# v0_4.net
KiCad netlist of a schematic drawn in EAGLE
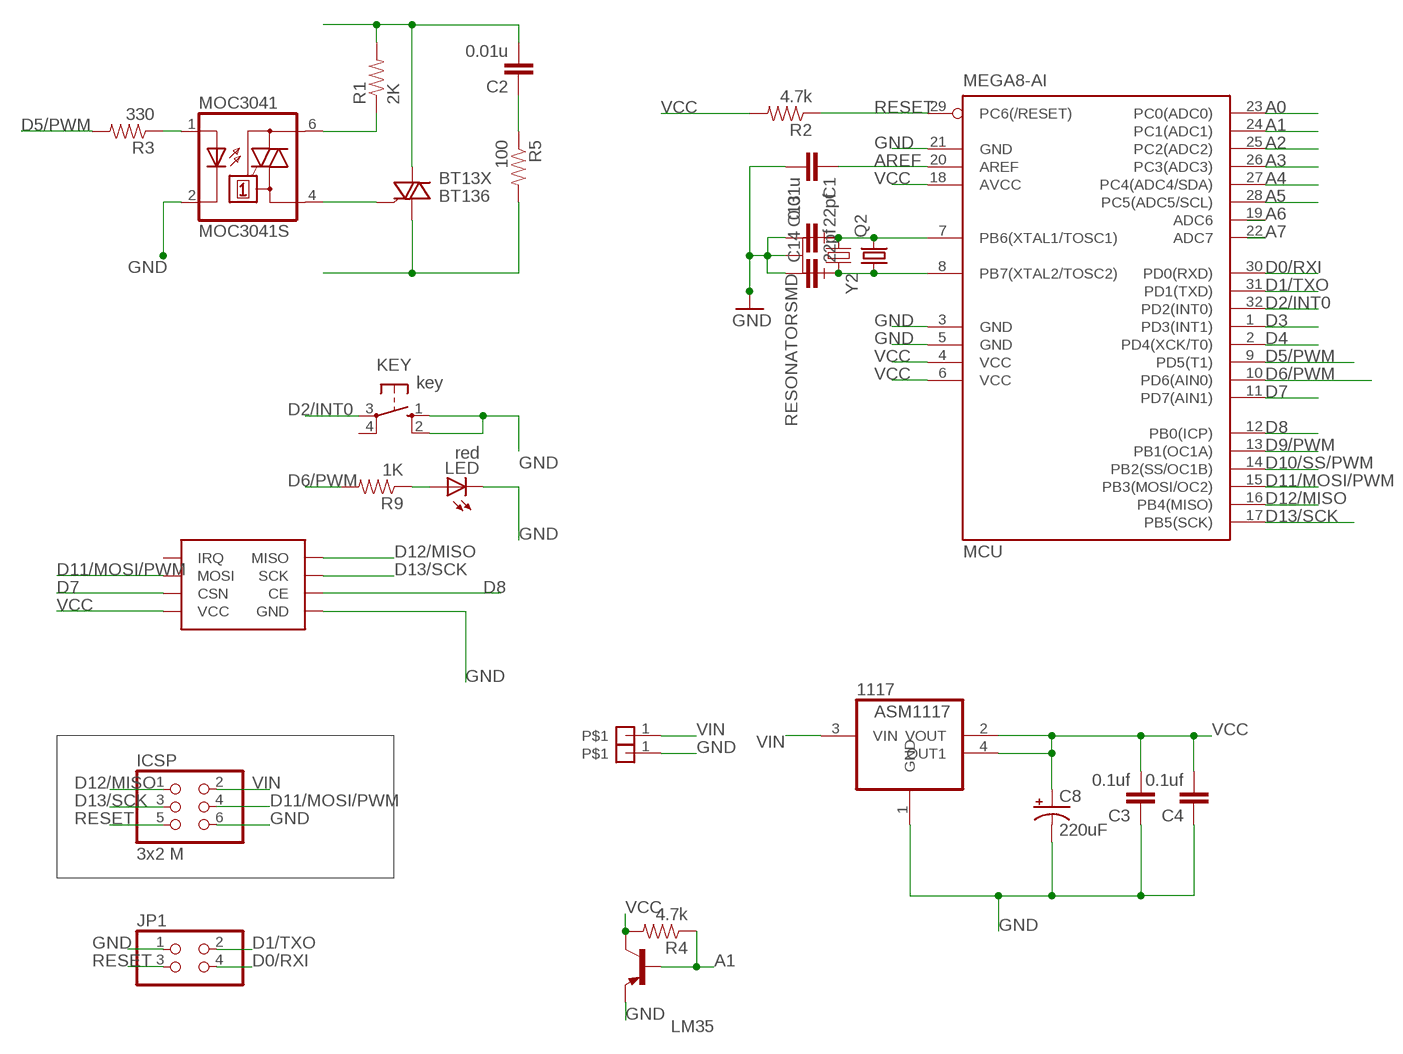
[diagram p0: schematic, sheet 1]

(export (version "E")
  (design (tool "Eeschema 10.0.6"))
  (components
    (comp (ref "1117")
      (value "ASM1117")
      (footprint "eagle-import:SOT223")
      (fields (field (name "MPN") "REG1117"))
      (libsource (lib "eagle-import") (part "ASM1117"))
    )
    (comp (ref "BT13X")
      (value "BT136")
      (footprint "eagle-import:TO252")
      (libsource (lib "eagle-import") (part "BT136"))
    )
    (comp (ref "C1")
      (value "0.01u")
      (footprint "eagle-import:0603-CAP")
      (libsource (lib "eagle-import") (part "MY2_CAP0603-CAP"))
    )
    (comp (ref "C2")
      (value "0.01u")
      (footprint "eagle-import:C050-024X044")
      (libsource (lib "eagle-import") (part "C-EU050-024X044"))
    )
    (comp (ref "C3")
      (value "0.1uf")
      (footprint "eagle-import:0603-CAP")
      (libsource (lib "eagle-import") (part "MY_CAP0603-CAP"))
    )
    (comp (ref "C4")
      (value "0.1uf")
      (footprint "eagle-import:0603-CAP")
      (libsource (lib "eagle-import") (part "MY_CAP0603-CAP"))
    )
    (comp (ref "C8")
      (value "220uF")
      (footprint "eagle-import:EIA3528")
      (libsource (lib "eagle-import") (part "CAP_POL3528"))
    )
    (comp (ref "C13")
      (value "22pf")
      (footprint "eagle-import:0603-CAP")
      (libsource (lib "eagle-import") (part "CAP0603-CAP"))
    )
    (comp (ref "C14")
      (value "22pf")
      (footprint "eagle-import:0603-CAP")
      (libsource (lib "eagle-import") (part "CAP0603-CAP"))
    )
    (comp (ref "ICSP")
      (value "3x2 M")
      (footprint "eagle-import:2X03")
      (libsource (lib "eagle-import") (part "PINHD-2X3"))
    )
    (comp (ref "JP1")
      (value "PINHD-2X2")
      (footprint "eagle-import:2X02")
      (libsource (lib "eagle-import") (part "PINHD-2X2"))
    )
    (comp (ref "KEY")
      (value "key")
      (footprint "eagle-import:B3F-10XX")
      (fields
        (field (name "MPN") "B3F-1000")
        (field (name "MPN_1") "B3F-1000")
        (field (name "OC_FARNELL") "176432")
        (field (name "OC_NEWARK") "36M3542")
      )
      (libsource (lib "eagle-import") (part "10-XX"))
    )
    (comp (ref "LED")
      (value "red")
      (footprint "eagle-import:LED3MM")
      (libsource (lib "eagle-import") (part "LED3MM"))
    )
    (comp (ref "LM35")
      (value "-PNP-TO92-E1")
      (footprint "eagle-import:TO92-E1")
      (libsource (lib "eagle-import") (part "-PNP-TO92-E1"))
    )
    (comp (ref "MCU")
      (value "MEGA8-AI")
      (footprint "eagle-import:TQFP32-08")
      (fields (field (name "MPN") "ATMEGA8-16AU"))
      (libsource (lib "eagle-import") (part "MEGA8-AI"))
    )
    (comp (ref "MOC3041")
      (value "MOC3041S")
      (footprint "eagle-import:DIL6-SMD")
      (fields
        (field (name "MF") "FAIRCHILD SEMICONDUCTOR")
        (field (name "MPN") "MOC3041S-M")
        (field (name "MF_1") "FAIRCHILD SEMICONDUCTOR")
        (field (name "MPN_1") "MOC3041S-M")
        (field (name "OC_NEWARK") "05C2885")
      )
      (libsource (lib "eagle-import") (part "MOC30S41"))
    )
    (comp (ref "Q2")
      (value "CRYSTALHC49S")
      (footprint "eagle-import:HC49_S")
      (libsource (lib "eagle-import") (part "CRYSTALHC49S"))
    )
    (comp (ref "R1")
      (value "2K")
      (footprint "eagle-import:AXIAL-0.3")
      (libsource (lib "eagle-import") (part "MY3_RESISTORPTH1"))
    )
    (comp (ref "R2")
      (value "4.7k")
      (footprint "eagle-import:0603-RES")
      (libsource (lib "eagle-import") (part "RESISTOR0603-RES"))
    )
    (comp (ref "R3")
      (value "330")
      (footprint "eagle-import:0603-RES")
      (libsource (lib "eagle-import") (part "RESISTOR0603-RES"))
    )
    (comp (ref "R4")
      (value "4.7k")
      (footprint "eagle-import:0603-RES")
      (libsource (lib "eagle-import") (part "RESISTOR0603-RES"))
    )
    (comp (ref "R5")
      (value "100")
      (footprint "eagle-import:AXIAL-0.3")
      (libsource (lib "eagle-import") (part "MY3_RESISTORPTH1"))
    )
    (comp (ref "R9")
      (value "1K")
      (footprint "eagle-import:0603-RES")
      (libsource (lib "eagle-import") (part "RESISTOR0603-RES"))
    )
    (comp (ref "U$3")
      (value "PIN1")
      (footprint "eagle-import:PIN1")
      (libsource (lib "eagle-import") (part "PIN1"))
    )
    (comp (ref "U$4")
      (value "PIN1")
      (footprint "eagle-import:PIN1")
      (libsource (lib "eagle-import") (part "PIN1"))
    )
    (comp (ref "U$6")
      (value "NRF")
      (footprint "eagle-import:NRF")
      (libsource (lib "eagle-import") (part "NRF"))
    )
    (comp (ref "Y2")
      (value "RESONATORSMD")
      (footprint "eagle-import:RESONATOR-SMD")
      (libsource (lib "eagle-import") (part "RESONATORSMD"))
    )
  )
  (nets
    (net (code "1") (name "/A0") (class "Default")
      (node (ref "MCU") (pin "23") (pinfunction "PC0(ADC0)_23") (pintype "bidirectional"))
    )
    (net (code "2") (name "/A1") (class "Default")
      (node (ref "LM35") (pin "2") (pinfunction "B_2") (pintype "passive"))
      (node (ref "MCU") (pin "24") (pinfunction "PC1(ADC1)_24") (pintype "bidirectional"))
      (node (ref "R4") (pin "1") (pinfunction "1_1") (pintype "passive"))
    )
    (net (code "3") (name "/A2") (class "Default")
      (node (ref "MCU") (pin "25") (pinfunction "PC2(ADC2)_25") (pintype "bidirectional"))
    )
    (net (code "4") (name "/A3") (class "Default")
      (node (ref "MCU") (pin "26") (pinfunction "PC3(ADC3)_26") (pintype "bidirectional"))
    )
    (net (code "5") (name "/A4") (class "Default")
      (node (ref "MCU") (pin "27") (pinfunction "PC4(ADC4/SDA)_27") (pintype "bidirectional"))
    )
    (net (code "6") (name "/A5") (class "Default")
      (node (ref "MCU") (pin "28") (pinfunction "PC5(ADC5/SCL)_28") (pintype "bidirectional"))
    )
    (net (code "7") (name "/A6") (class "Default")
      (node (ref "MCU") (pin "19") (pinfunction "ADC6_19") (pintype "bidirectional"))
    )
    (net (code "8") (name "/A7") (class "Default")
      (node (ref "MCU") (pin "22") (pinfunction "ADC7_22") (pintype "bidirectional"))
    )
    (net (code "9") (name "/AREF") (class "Default")
      (node (ref "C1") (pin "1") (pinfunction "1_1") (pintype "passive"))
      (node (ref "MCU") (pin "20") (pinfunction "AREF_20") (pintype "passive"))
    )
    (net (code "10") (name "/D0{slash}RXI") (class "Default")
      (node (ref "JP1") (pin "4") (pinfunction "4_4") (pintype "passive"))
      (node (ref "MCU") (pin "30") (pinfunction "PD0(RXD)_30") (pintype "bidirectional"))
    )
    (net (code "11") (name "/D1{slash}TXO") (class "Default")
      (node (ref "JP1") (pin "2") (pinfunction "2_2") (pintype "passive"))
      (node (ref "MCU") (pin "31") (pinfunction "PD1(TXD)_31") (pintype "bidirectional"))
    )
    (net (code "12") (name "/D2{slash}INT0") (class "Default")
      (node (ref "KEY") (pin "3") (pinfunction "P_3") (pintype "passive"))
      (node (ref "MCU") (pin "32") (pinfunction "PD2(INT0)_32") (pintype "bidirectional"))
    )
    (net (code "13") (name "/D3") (class "Default")
      (node (ref "MCU") (pin "1") (pinfunction "PD3(INT1)_1") (pintype "bidirectional"))
    )
    (net (code "14") (name "/D4") (class "Default")
      (node (ref "MCU") (pin "2") (pinfunction "PD4(XCK/T0)_2") (pintype "bidirectional"))
    )
    (net (code "15") (name "/D5{slash}PWM") (class "Default")
      (node (ref "MCU") (pin "9") (pinfunction "PD5(T1)_9") (pintype "bidirectional"))
      (node (ref "R3") (pin "2") (pinfunction "2_2") (pintype "passive"))
    )
    (net (code "16") (name "/D6{slash}PWM") (class "Default")
      (node (ref "MCU") (pin "10") (pinfunction "PD6(AIN0)_10") (pintype "bidirectional"))
      (node (ref "R9") (pin "2") (pinfunction "2_2") (pintype "passive"))
    )
    (net (code "17") (name "/D7") (class "Default")
      (node (ref "MCU") (pin "11") (pinfunction "PD7(AIN1)_11") (pintype "bidirectional"))
      (node (ref "U$6") (pin "P$4") (pinfunction "CSN_P$4") (pintype "bidirectional"))
    )
    (net (code "18") (name "/D8") (class "Default")
      (node (ref "MCU") (pin "12") (pinfunction "PB0(ICP)_12") (pintype "bidirectional"))
      (node (ref "U$6") (pin "P$3") (pinfunction "CE_P$3") (pintype "bidirectional"))
    )
    (net (code "19") (name "/D9{slash}PWM") (class "Default")
      (node (ref "MCU") (pin "13") (pinfunction "PB1(OC1A)_13") (pintype "bidirectional"))
    )
    (net (code "20") (name "/D10{slash}SS{slash}PWM") (class "Default")
      (node (ref "MCU") (pin "14") (pinfunction "PB2(SS/OC1B)_14") (pintype "bidirectional"))
    )
    (net (code "21") (name "/D11{slash}MOSI{slash}PWM") (class "Default")
      (node (ref "ICSP") (pin "4") (pinfunction "4_4") (pintype "passive"))
      (node (ref "MCU") (pin "15") (pinfunction "PB3(MOSI/OC2)_15") (pintype "bidirectional"))
      (node (ref "U$6") (pin "P$6") (pinfunction "MOSI_P$6") (pintype "bidirectional"))
    )
    (net (code "22") (name "/D12{slash}MISO") (class "Default")
      (node (ref "ICSP") (pin "1") (pinfunction "1_1") (pintype "passive"))
      (node (ref "MCU") (pin "16") (pinfunction "PB4(MISO)_16") (pintype "bidirectional"))
      (node (ref "U$6") (pin "P$7") (pinfunction "MISO_P$7") (pintype "bidirectional"))
    )
    (net (code "23") (name "/D13{slash}SCK") (class "Default")
      (node (ref "ICSP") (pin "3") (pinfunction "3_3") (pintype "passive"))
      (node (ref "MCU") (pin "17") (pinfunction "PB5(SCK)_17") (pintype "bidirectional"))
      (node (ref "U$6") (pin "P$5") (pinfunction "SCK_P$5") (pintype "bidirectional"))
    )
    (net (code "24") (name "/RESET") (class "Default")
      (node (ref "ICSP") (pin "5") (pinfunction "5_5") (pintype "passive"))
      (node (ref "JP1") (pin "3") (pinfunction "3_3") (pintype "passive"))
      (node (ref "MCU") (pin "29") (pinfunction "PC6(/RESET)_29") (pintype "bidirectional"))
      (node (ref "R2") (pin "1") (pinfunction "1_1") (pintype "passive"))
    )
    (net (code "25") (name "/VCC") (class "Default")
      (node (ref "1117") (pin "2") (pinfunction "VOUT_2") (pintype "output"))
      (node (ref "1117") (pin "4") (pinfunction "OUT1_4") (pintype "bidirectional"))
      (node (ref "C3") (pin "2") (pinfunction "2_2") (pintype "passive"))
      (node (ref "C4") (pin "2") (pinfunction "2_2") (pintype "passive"))
      (node (ref "C8") (pin "A") (pinfunction "+_A") (pintype "passive"))
      (node (ref "LM35") (pin "1") (pinfunction "C_1") (pintype "passive"))
      (node (ref "MCU") (pin "18") (pinfunction "AVCC_18") (pintype "power_in"))
      (node (ref "MCU") (pin "4") (pinfunction "VCC_4") (pintype "power_in"))
      (node (ref "MCU") (pin "6") (pinfunction "VCC_6") (pintype "power_in"))
      (node (ref "R2") (pin "2") (pinfunction "2_2") (pintype "passive"))
      (node (ref "R4") (pin "2") (pinfunction "2_2") (pintype "passive"))
      (node (ref "U$6") (pin "P$2") (pinfunction "VCC_P$2") (pintype "bidirectional"))
    )
    (net (code "26") (name "/VIN") (class "Default")
      (node (ref "1117") (pin "3") (pinfunction "VIN_3") (pintype "input"))
      (node (ref "ICSP") (pin "2") (pinfunction "2_2") (pintype "passive"))
      (node (ref "U$3") (pin "1") (pinfunction "P$1_1") (pintype "bidirectional"))
    )
    (net (code "27") (name "GND") (class "Default")
      (node (ref "1117") (pin "1") (pinfunction "GND_1") (pintype "power_in"))
      (node (ref "C1") (pin "2") (pinfunction "2_2") (pintype "passive"))
      (node (ref "C13") (pin "1") (pinfunction "1_1") (pintype "passive"))
      (node (ref "C14") (pin "1") (pinfunction "1_1") (pintype "passive"))
      (node (ref "C3") (pin "1") (pinfunction "1_1") (pintype "passive"))
      (node (ref "C4") (pin "1") (pinfunction "1_1") (pintype "passive"))
      (node (ref "C8") (pin "C") (pinfunction "-_C") (pintype "passive"))
      (node (ref "ICSP") (pin "6") (pinfunction "6_6") (pintype "passive"))
      (node (ref "JP1") (pin "1") (pinfunction "1_1") (pintype "passive"))
      (node (ref "KEY") (pin "1") (pinfunction "S_1") (pintype "passive"))
      (node (ref "KEY") (pin "2") (pinfunction "S1_2") (pintype "passive"))
      (node (ref "LED") (pin "K") (pinfunction "C_K") (pintype "passive"))
      (node (ref "LM35") (pin "3") (pinfunction "E_3") (pintype "passive"))
      (node (ref "MCU") (pin "21") (pinfunction "GND_21") (pintype "power_in"))
      (node (ref "MCU") (pin "3") (pinfunction "GND_3") (pintype "power_in"))
      (node (ref "MCU") (pin "5") (pinfunction "GND_5") (pintype "power_in"))
      (node (ref "MOC3041") (pin "2") (pinfunction "C_2") (pintype "passive"))
      (node (ref "U$4") (pin "1") (pinfunction "P$1_1") (pintype "bidirectional"))
      (node (ref "U$6") (pin "P$1") (pinfunction "GND_P$1") (pintype "bidirectional"))
      (node (ref "Y2") (pin "2") (pinfunction "2_2") (pintype "passive"))
    )
    (net (code "28") (name "Net-(BT13X-A1)") (class "Default")
      (node (ref "BT13X") (pin "1") (pinfunction "A1_1") (pintype "passive"))
      (node (ref "R5") (pin "P$2") (pinfunction "2_P$2") (pintype "passive"))
    )
    (net (code "29") (name "Net-(BT13X-A2)") (class "Default")
      (node (ref "BT13X") (pin "3") (pinfunction "A2_3") (pintype "passive"))
      (node (ref "C2") (pin "2") (pinfunction "2_2") (pintype "passive"))
      (node (ref "R1") (pin "P$2") (pinfunction "2_P$2") (pintype "passive"))
    )
    (net (code "30") (name "Net-(BT13X-G)") (class "Default")
      (node (ref "BT13X") (pin "2") (pinfunction "G_2") (pintype "passive"))
      (node (ref "MOC3041") (pin "4") (pinfunction "A1_4") (pintype "passive"))
    )
    (net (code "31") (name "Net-(LED-PadA)") (class "Default")
      (node (ref "LED") (pin "A") (pinfunction "A_A") (pintype "passive"))
      (node (ref "R9") (pin "1") (pinfunction "1_1") (pintype "passive"))
    )
    (net (code "32") (name "Net-(MCU-PB6(XTAL1{slash}TOSC1))") (class "Default")
      (node (ref "C13") (pin "2") (pinfunction "2_2") (pintype "passive"))
      (node (ref "MCU") (pin "7") (pinfunction "PB6(XTAL1/TOSC1)_7") (pintype "bidirectional"))
      (node (ref "Q2") (pin "2") (pinfunction "2_2") (pintype "passive"))
      (node (ref "Y2") (pin "1") (pinfunction "1_1") (pintype "passive"))
    )
    (net (code "33") (name "Net-(MCU-PB7(XTAL2{slash}TOSC2))") (class "Default")
      (node (ref "C14") (pin "2") (pinfunction "2_2") (pintype "passive"))
      (node (ref "MCU") (pin "8") (pinfunction "PB7(XTAL2/TOSC2)_8") (pintype "bidirectional"))
      (node (ref "Q2") (pin "1") (pinfunction "1_1") (pintype "passive"))
      (node (ref "Y2") (pin "3") (pinfunction "3_3") (pintype "passive"))
    )
    (net (code "34") (name "Net-(MOC3041-A)") (class "Default")
      (node (ref "MOC3041") (pin "1") (pinfunction "A_1") (pintype "passive"))
      (node (ref "R3") (pin "1") (pinfunction "1_1") (pintype "passive"))
    )
    (net (code "35") (name "Net-(MOC3041-A2)") (class "Default")
      (node (ref "MOC3041") (pin "6") (pinfunction "A2_6") (pintype "passive"))
      (node (ref "R1") (pin "P$1") (pinfunction "1_P$1") (pintype "passive"))
    )
    (net (code "36") (name "Net-(R5-1)") (class "Default")
      (node (ref "C2") (pin "1") (pinfunction "1_1") (pintype "passive"))
      (node (ref "R5") (pin "P$1") (pinfunction "1_P$1") (pintype "passive"))
    )
    (net (code "37") (name "unconnected-(KEY-P1-Pad4)") (class "Default")
      (node (ref "KEY") (pin "4") (pinfunction "P1_4") (pintype "passive"))
    )
    (net (code "38") (name "unconnected-(U$6-IRQ-PadP$8)") (class "Default")
      (node (ref "U$6") (pin "P$8") (pinfunction "IRQ_P$8") (pintype "bidirectional"))
    )
  )
)
